# SPH0641LM4H_MEMS_Microphone.net
KiCad netlist of a schematic drawn in Altium Designer
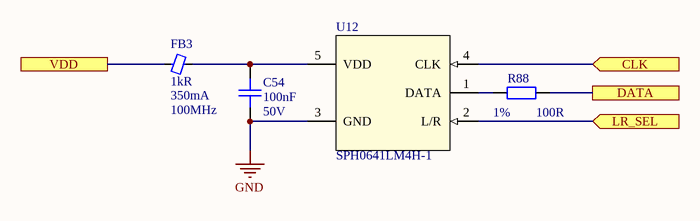
[diagram p0: SPH0641LM4H_MEMS_Microphone.SchDoc]

(export (version "E")
  (design (tool "Eeschema 10.0.6"))
  (components
    (comp (ref "C54")
      (value "CAP CER 0.1UF 50V X7R 0402")
      (footprint "C0402")
      (description "0.1µF ±10% 50V Ceramic Capacitor X7R 0402 (1005 Metric)")
      (fields
        (field (name "MANUFACTURER") "TDK")
        (field (name "MANUFACTURER PART NUMBER") "CGA2B3X7R1H104K050BB")
        (field (name "CAPACITANCE") "100nF")
        (field (name "VOLTAGE") "50V")
      )
      (libsource (lib "capacitors_smd") (part "CAP CER 0.1UF 50V X7R 0402"))
    )
    (comp (ref "FB3")
      (value "FERRITE BEAD 1 KOHM 0402 1LN")
      (footprint "L0402")
      (description "1 kOhms @ 100MHz 1  Ferrite Bead 0402 (1005 Metric) 350mA 490mOhm")
      (fields
        (field (name "MANUFACTURER") "Murata")
        (field (name "MANUFACTURER PART NUMBER") "BLM15AX102SN1D")
        (field (name "IMPEDANCE") "1kR")
        (field (name "MAX DC CURRENT") "350mA")
        (field (name "TEST FREQUENCY") "100MHz")
      )
      (libsource (lib "Control_Board_Model") (part "FERRITE BEAD 1 KOHM 0402 1LN"))
    )
    (comp (ref "R88")
      (value "RES SMD 100 OHM 1% 1/16W 0402")
      (footprint "R0402")
      (description "100 Ohms ±1% 0.063W, 1/16W Chip Resistor 0402 (1005 Metric) Moisture Resistant Thick Film")
      (fields
        (field (name "MANUFACTURER") "Yageo")
        (field (name "MANUFACTURER PART NUMBER") "RC0402FR-07100RL")
        (field (name "TOLERANCE") "1%")
        (field (name "RESISTANCE") "100R")
      )
      (libsource (lib "Control_Board_Model") (part "RES SMD 100 OHM 1% 1/16W 0402"))
    )
    (comp (ref "U12")
      (value "SPH0641LM4H-1")
      (footprint "MIC_SPH0641LM4H-1")
      (description "100 Hz ~ 10 kHz Microphone 1.62 V ~ 3.6 V ()")
      (fields (field (name "MANUFACTURER") "Infineon"))
      (libsource (lib "Control_Board_Model") (part "IC SPH0641LM4H-1 MORELLO MIC MULTIMODE DGT BOT PT"))
    )
  )
  (nets
    (net (code "1") (name "/CLK") (class "Default")
      (node (ref "U12") (pin "4") (pinfunction "CLK_4") (pintype "input"))
    )
    (net (code "2") (name "/DATA") (class "Default")
      (node (ref "R88") (pin "1") (pinfunction "1_1") (pintype "passive"))
    )
    (net (code "3") (name "/LR_SEL") (class "Default")
      (node (ref "U12") (pin "2") (pinfunction "L/R_2") (pintype "input"))
    )
    (net (code "4") (name "/VDD") (class "Default")
      (node (ref "FB3") (pin "1") (pinfunction "1_1") (pintype "passive"))
    )
    (net (code "5") (name "GND") (class "Default")
      (node (ref "C54") (pin "1") (pinfunction "1_1") (pintype "passive"))
      (node (ref "U12") (pin "3") (pinfunction "GND_3") (pintype "power_in"))
    )
    (net (code "6") (name "Net-(U12-DATA)") (class "Default")
      (node (ref "R88") (pin "2") (pinfunction "2_2") (pintype "passive"))
      (node (ref "U12") (pin "1") (pinfunction "DATA_1") (pintype "tri_state"))
    )
    (net (code "7") (name "Net-(U12-VDD)") (class "Default")
      (node (ref "C54") (pin "2") (pinfunction "2_2") (pintype "passive"))
      (node (ref "FB3") (pin "2") (pinfunction "2_2") (pintype "passive"))
      (node (ref "U12") (pin "5") (pinfunction "VDD_5") (pintype "power_in"))
    )
  )
)
